# pam2803-boost-driver-13mm-mk-1_0.net
KiCad netlist of a schematic drawn in EAGLE
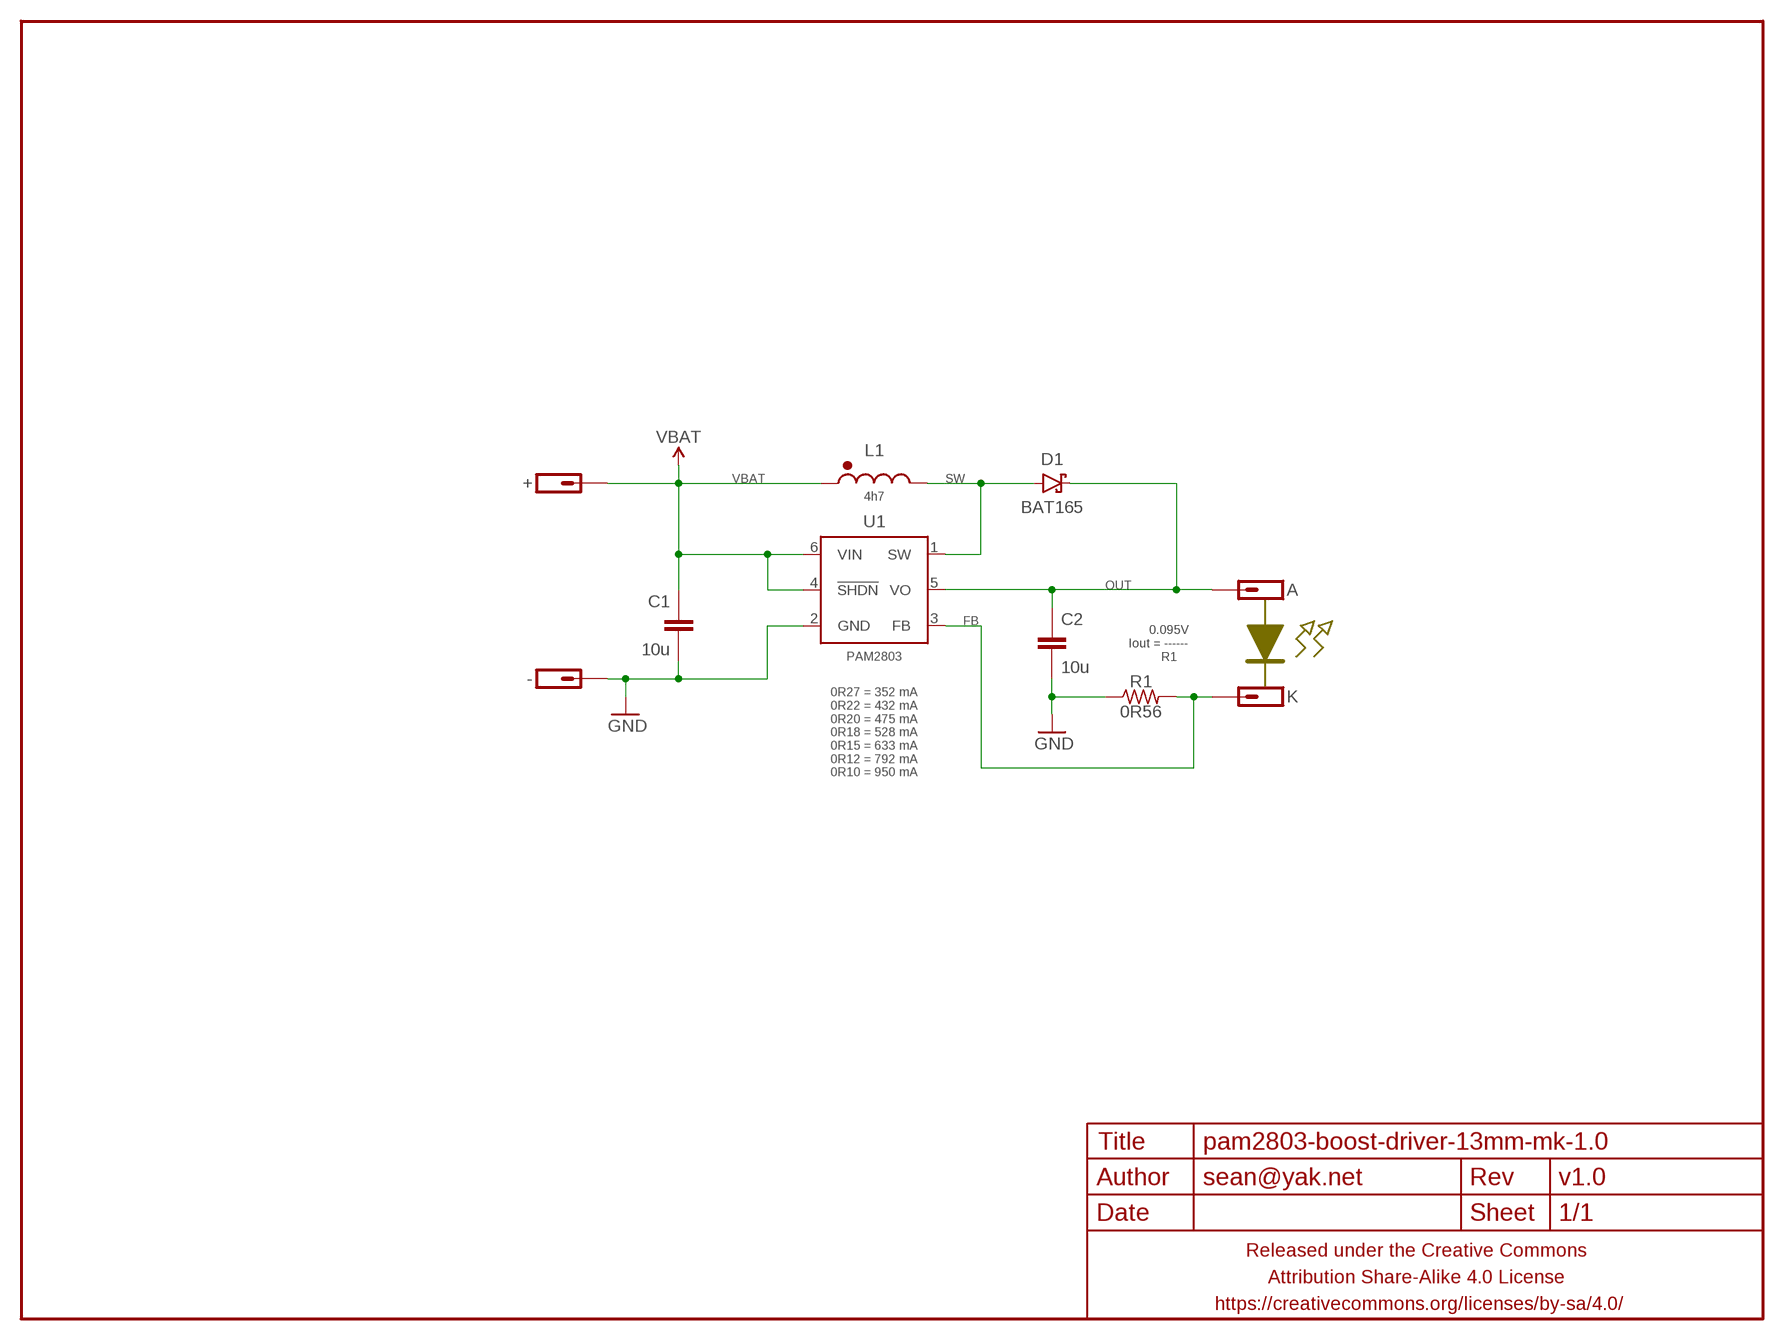
[diagram p0: schematic, sheet 1]

(export (version "E")
  (design (tool "Eeschema 10.0.6"))
  (components
    (comp (ref "+")
      (value "M01NOT-A-VIA-NOPE")
      (footprint "eagle-import:1X01_NOSILK_NOSTOP")
      (libsource (lib "eagle-import") (part "M01NOT-A-VIA-NOPE"))
    )
    (comp (ref "-")
      (value "M01NOT-A-VIA-NOPE")
      (footprint "eagle-import:1X01_NOSILK_NOSTOP")
      (libsource (lib "eagle-import") (part "M01NOT-A-VIA-NOPE"))
    )
    (comp (ref "A")
      (value "M01SMD-1.5MM-DIA-NS")
      (footprint "eagle-import:1X01-SMD-1.5MM-DIA-NS")
      (libsource (lib "eagle-import") (part "M01SMD-1.5MM-DIA-NS"))
    )
    (comp (ref "C1")
      (value "10u")
      (footprint "eagle-import:C0805-TIGHTER")
      (libsource (lib "eagle-import") (part "CAPACITOR-CERAMICC0805-TIGHTER"))
    )
    (comp (ref "C2")
      (value "10u")
      (footprint "eagle-import:C0805-TIGHTER")
      (libsource (lib "eagle-import") (part "CAPACITOR-CERAMICC0805-TIGHTER"))
    )
    (comp (ref "D1")
      (value "BAT165")
      (footprint "eagle-import:SOD323-SCHOTTKY")
      (libsource (lib "eagle-import") (part "DIODE-SCHOTTKYSOD323"))
    )
    (comp (ref "FRAME1")
      (value "FRAME-LETTERNO_PACKAGE")
      (footprint "eagle-import:DUMMY")
      (fields (field (name "DESIGNER") "sean@yak.net") (field (name "VERSION") "v1.0"))
      (libsource (lib "eagle-import") (part "FRAME-LETTERNO_PACKAGE"))
    )
    (comp (ref "K")
      (value "M01SMD-1.5MM-DIA-NS")
      (footprint "eagle-import:1X01-SMD-1.5MM-DIA-NS")
      (libsource (lib "eagle-import") (part "M01SMD-1.5MM-DIA-NS"))
    )
    (comp (ref "L1")
      (value "4h7")
      (footprint "eagle-import:EPL2014")
      (libsource (lib "eagle-import") (part "INDUCTOREPL2014"))
    )
    (comp (ref "R1")
      (value "0R56")
      (footprint "eagle-import:R0603-TIGHTER")
      (libsource (lib "eagle-import") (part "RESISTORR0603-TIGHTER"))
    )
    (comp (ref "U1")
      (value "PAM2803")
      (footprint "eagle-import:SOT23-6")
      (libsource (lib "eagle-import") (part "PAM2803SOT23-6"))
    )
  )
  (nets
    (net (code "1") (name "/FB") (class "Default")
      (node (ref "K") (pin "P$1") (pinfunction "1_P$1") (pintype "passive"))
      (node (ref "R1") (pin "2") (pinfunction "2_2") (pintype "passive"))
      (node (ref "U1") (pin "3") (pinfunction "FB_3") (pintype "bidirectional"))
    )
    (net (code "2") (name "/OUT") (class "Default")
      (node (ref "A") (pin "P$1") (pinfunction "1_P$1") (pintype "passive"))
      (node (ref "C2") (pin "1") (pinfunction "1_1") (pintype "passive"))
      (node (ref "D1") (pin "C") (pinfunction "C_C") (pintype "passive"))
      (node (ref "U1") (pin "5") (pinfunction "VO_5") (pintype "bidirectional"))
    )
    (net (code "3") (name "/SW") (class "Default")
      (node (ref "D1") (pin "A") (pinfunction "A_A") (pintype "passive"))
      (node (ref "L1") (pin "P$2") (pinfunction "2_P$2") (pintype "passive"))
      (node (ref "U1") (pin "1") (pinfunction "SW_1") (pintype "bidirectional"))
    )
    (net (code "4") (name "GND") (class "Default")
      (node (ref "-") (pin "P$1") (pinfunction "1_P$1") (pintype "passive"))
      (node (ref "C1") (pin "2") (pinfunction "2_2") (pintype "passive"))
      (node (ref "C2") (pin "2") (pinfunction "2_2") (pintype "passive"))
      (node (ref "R1") (pin "1") (pinfunction "1_1") (pintype "passive"))
      (node (ref "U1") (pin "2") (pinfunction "GND_2") (pintype "bidirectional"))
    )
    (net (code "5") (name "VBAT") (class "Default")
      (node (ref "+") (pin "P$1") (pinfunction "1_P$1") (pintype "passive"))
      (node (ref "C1") (pin "1") (pinfunction "1_1") (pintype "passive"))
      (node (ref "L1") (pin "P$1") (pinfunction "1_P$1") (pintype "passive"))
      (node (ref "U1") (pin "4") (pinfunction "~{SHDN}_4") (pintype "bidirectional"))
      (node (ref "U1") (pin "6") (pinfunction "VIN_6") (pintype "bidirectional"))
    )
  )
)
